# Cell_Connections.net
KiCad netlist of a schematic drawn in Altium Designer
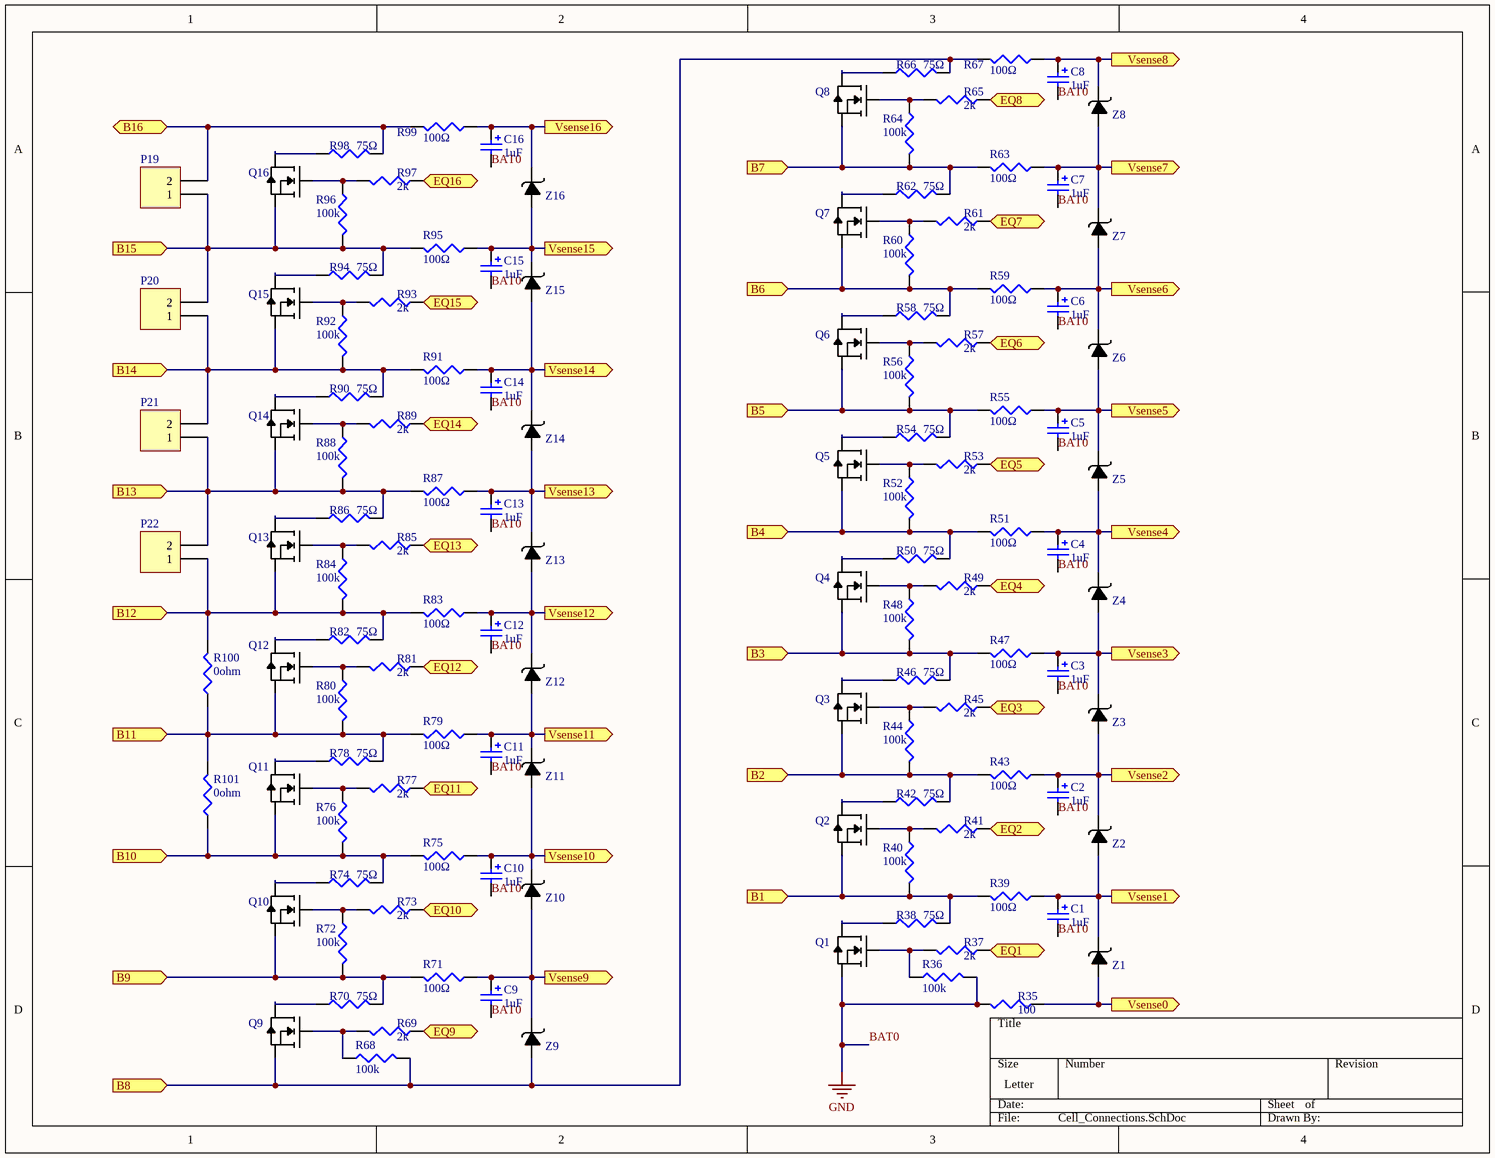
[diagram p0: Cell_Connections.SchDoc]

(export (version "E")
  (design (tool "Eeschema 10.0.6"))
  (components
    (comp (ref "C1")
      (value "1uF")
      (footprint "SMD1206 Polarized")
      (description "Polarized Capacitor (Surface Mount)")
      (fields (field (name "Comment") "Cap"))
      (libsource (lib "Components") (part "Capacitor Polarized"))
    )
    (comp (ref "C2")
      (value "1uF")
      (footprint "SMD1206 Polarized")
      (description "Polarized Capacitor (Surface Mount)")
      (fields (field (name "Comment") "Cap"))
      (libsource (lib "Components") (part "Capacitor Polarized"))
    )
    (comp (ref "C3")
      (value "1uF")
      (footprint "SMD1206 Polarized")
      (description "Polarized Capacitor (Surface Mount)")
      (fields (field (name "Comment") "Cap"))
      (libsource (lib "Components") (part "Capacitor Polarized"))
    )
    (comp (ref "C4")
      (value "1uF")
      (footprint "SMD1206 Polarized")
      (description "Polarized Capacitor (Surface Mount)")
      (fields (field (name "Comment") "Cap"))
      (libsource (lib "Components") (part "Capacitor Polarized"))
    )
    (comp (ref "C5")
      (value "1uF")
      (footprint "SMD1206 Polarized")
      (description "Polarized Capacitor (Surface Mount)")
      (fields (field (name "Comment") "Cap"))
      (libsource (lib "Components") (part "Capacitor Polarized"))
    )
    (comp (ref "C6")
      (value "1uF")
      (footprint "SMD1206 Polarized")
      (description "Polarized Capacitor (Surface Mount)")
      (fields (field (name "Comment") "Cap"))
      (libsource (lib "Components") (part "Capacitor Polarized"))
    )
    (comp (ref "C7")
      (value "1uF")
      (footprint "SMD1206 Polarized")
      (description "Polarized Capacitor (Surface Mount)")
      (fields (field (name "Comment") "Cap"))
      (libsource (lib "Components") (part "Capacitor Polarized"))
    )
    (comp (ref "C8")
      (value "1uF")
      (footprint "SMD1206 Polarized")
      (description "Polarized Capacitor (Surface Mount)")
      (fields (field (name "Comment") "Cap"))
      (libsource (lib "Components") (part "Capacitor Polarized"))
    )
    (comp (ref "C9")
      (value "1uF")
      (footprint "SMD1206 Polarized")
      (description "Polarized Capacitor (Surface Mount)")
      (fields (field (name "Comment") "Cap"))
      (libsource (lib "Components") (part "Capacitor Polarized"))
    )
    (comp (ref "C10")
      (value "1uF")
      (footprint "SMD1206 Polarized")
      (description "Polarized Capacitor (Surface Mount)")
      (fields (field (name "Comment") "Cap"))
      (libsource (lib "Components") (part "Capacitor Polarized"))
    )
    (comp (ref "C11")
      (value "1uF")
      (footprint "SMD1206 Polarized")
      (description "Polarized Capacitor (Surface Mount)")
      (fields (field (name "Comment") "Cap"))
      (libsource (lib "Components") (part "Capacitor Polarized"))
    )
    (comp (ref "C12")
      (value "1uF")
      (footprint "SMD1206 Polarized")
      (description "Polarized Capacitor (Surface Mount)")
      (fields (field (name "Comment") "Cap"))
      (libsource (lib "Components") (part "Capacitor Polarized"))
    )
    (comp (ref "C13")
      (value "1uF")
      (footprint "SMD1206 Polarized")
      (description "Polarized Capacitor (Surface Mount)")
      (fields (field (name "Comment") "Cap"))
      (libsource (lib "Components") (part "Capacitor Polarized"))
    )
    (comp (ref "C14")
      (value "1uF")
      (footprint "SMD1206 Polarized")
      (description "Polarized Capacitor (Surface Mount)")
      (fields (field (name "Comment") "Cap"))
      (libsource (lib "Components") (part "Capacitor Polarized"))
    )
    (comp (ref "C15")
      (value "1uF")
      (footprint "SMD1206 Polarized")
      (description "Polarized Capacitor (Surface Mount)")
      (fields (field (name "Comment") "Cap"))
      (libsource (lib "Components") (part "Capacitor Polarized"))
    )
    (comp (ref "C16")
      (value "1uF")
      (footprint "SMD1206 Polarized")
      (description "Polarized Capacitor (Surface Mount)")
      (fields (field (name "Comment") "Cap"))
      (libsource (lib "Components") (part "Capacitor Polarized"))
    )
    (comp (ref "P19")
      (value "Header")
      (footprint "Header 2x1")
      (description "Header, 2-Pin")
      (libsource (lib "Components") (part "Header 2x1"))
    )
    (comp (ref "P20")
      (value "Header")
      (footprint "Header 2x1")
      (description "Header, 2-Pin")
      (libsource (lib "Components") (part "Header 2x1"))
    )
    (comp (ref "P21")
      (value "Header")
      (footprint "Header 2x1")
      (description "Header, 2-Pin")
      (libsource (lib "Components") (part "Header 2x1"))
    )
    (comp (ref "P22")
      (value "Header")
      (footprint "Header 2x1")
      (description "Header, 2-Pin")
      (libsource (lib "Components") (part "Header 2x1"))
    )
    (comp (ref "Q1")
      (value "Transistor")
      (footprint "DPAK M:Transistor 3-Lead")
      (libsource (lib "Components") (part "Transistor"))
    )
    (comp (ref "Q2")
      (value "Transistor")
      (footprint "DPAK M:Transistor 3-Lead")
      (libsource (lib "Components") (part "Transistor"))
    )
    (comp (ref "Q3")
      (value "Transistor")
      (footprint "DPAK M:Transistor 3-Lead")
      (libsource (lib "Components") (part "Transistor"))
    )
    (comp (ref "Q4")
      (value "Transistor")
      (footprint "DPAK M:Transistor 3-Lead")
      (libsource (lib "Components") (part "Transistor"))
    )
    (comp (ref "Q5")
      (value "Transistor")
      (footprint "DPAK M:Transistor 3-Lead")
      (libsource (lib "Components") (part "Transistor"))
    )
    (comp (ref "Q6")
      (value "Transistor")
      (footprint "DPAK M:Transistor 3-Lead")
      (libsource (lib "Components") (part "Transistor"))
    )
    (comp (ref "Q7")
      (value "Transistor")
      (footprint "DPAK M:Transistor 3-Lead")
      (libsource (lib "Components") (part "Transistor"))
    )
    (comp (ref "Q8")
      (value "Transistor")
      (footprint "DPAK M:Transistor 3-Lead")
      (libsource (lib "Components") (part "Transistor"))
    )
    (comp (ref "Q9")
      (value "Transistor")
      (footprint "DPAK M:Transistor 3-Lead")
      (libsource (lib "Components") (part "Transistor"))
    )
    (comp (ref "Q10")
      (value "Transistor")
      (footprint "DPAK M:Transistor 3-Lead")
      (libsource (lib "Components") (part "Transistor"))
    )
    (comp (ref "Q11")
      (value "Transistor")
      (footprint "DPAK M:Transistor 3-Lead")
      (libsource (lib "Components") (part "Transistor"))
    )
    (comp (ref "Q12")
      (value "Transistor")
      (footprint "DPAK M:Transistor 3-Lead")
      (libsource (lib "Components") (part "Transistor"))
    )
    (comp (ref "Q13")
      (value "Transistor")
      (footprint "DPAK M:Transistor 3-Lead")
      (libsource (lib "Components") (part "Transistor"))
    )
    (comp (ref "Q14")
      (value "Transistor")
      (footprint "DPAK M:Transistor 3-Lead")
      (libsource (lib "Components") (part "Transistor"))
    )
    (comp (ref "Q15")
      (value "Transistor")
      (footprint "DPAK M:Transistor 3-Lead")
      (libsource (lib "Components") (part "Transistor"))
    )
    (comp (ref "Q16")
      (value "Transistor")
      (footprint "DPAK M:Transistor 3-Lead")
      (libsource (lib "Components") (part "Transistor"))
    )
    (comp (ref "R35")
      (value "100")
      (footprint "SMD0603")
      (description "Resistor")
      (fields (field (name "Comment") "Res"))
      (libsource (lib "Components") (part "Resistor"))
    )
    (comp (ref "R36")
      (value "100k")
      (footprint "SMD0603")
      (description "Resistor")
      (fields (field (name "Comment") "Res"))
      (libsource (lib "Components") (part "Resistor"))
    )
    (comp (ref "R37")
      (value "2k")
      (footprint "SMD0603")
      (description "Resistor")
      (fields (field (name "Comment") "Res"))
      (libsource (lib "Components") (part "Resistor"))
    )
    (comp (ref "R38")
      (value "75Ω")
      (footprint "SMD0603")
      (description "Resistor")
      (fields (field (name "Comment") "Res"))
      (libsource (lib "Components") (part "Resistor"))
    )
    (comp (ref "R39")
      (value "100Ω")
      (footprint "SMD0603")
      (description "Resistor")
      (fields (field (name "Comment") "Res"))
      (libsource (lib "Components") (part "Resistor"))
    )
    (comp (ref "R40")
      (value "100k")
      (footprint "SMD0603")
      (description "Resistor")
      (fields (field (name "Comment") "Res"))
      (libsource (lib "Components") (part "Resistor"))
    )
    (comp (ref "R41")
      (value "2k")
      (footprint "SMD0603")
      (description "Resistor")
      (fields (field (name "Comment") "Res"))
      (libsource (lib "Components") (part "Resistor"))
    )
    (comp (ref "R42")
      (value "75Ω")
      (footprint "SMD0603")
      (description "Resistor")
      (fields (field (name "Comment") "Res"))
      (libsource (lib "Components") (part "Resistor"))
    )
    (comp (ref "R43")
      (value "100Ω")
      (footprint "SMD0603")
      (description "Resistor")
      (fields (field (name "Comment") "Res"))
      (libsource (lib "Components") (part "Resistor"))
    )
    (comp (ref "R44")
      (value "100k")
      (footprint "SMD0603")
      (description "Resistor")
      (fields (field (name "Comment") "Res"))
      (libsource (lib "Components") (part "Resistor"))
    )
    (comp (ref "R45")
      (value "2k")
      (footprint "SMD0603")
      (description "Resistor")
      (fields (field (name "Comment") "Res"))
      (libsource (lib "Components") (part "Resistor"))
    )
    (comp (ref "R46")
      (value "75Ω")
      (footprint "SMD0603")
      (description "Resistor")
      (fields (field (name "Comment") "Res"))
      (libsource (lib "Components") (part "Resistor"))
    )
    (comp (ref "R47")
      (value "100Ω")
      (footprint "SMD0603")
      (description "Resistor")
      (fields (field (name "Comment") "Res"))
      (libsource (lib "Components") (part "Resistor"))
    )
    (comp (ref "R48")
      (value "100k")
      (footprint "SMD0603")
      (description "Resistor")
      (fields (field (name "Comment") "Res"))
      (libsource (lib "Components") (part "Resistor"))
    )
    (comp (ref "R49")
      (value "2k")
      (footprint "SMD0603")
      (description "Resistor")
      (fields (field (name "Comment") "Res"))
      (libsource (lib "Components") (part "Resistor"))
    )
    (comp (ref "R50")
      (value "75Ω")
      (footprint "SMD0603")
      (description "Resistor")
      (fields (field (name "Comment") "Res"))
      (libsource (lib "Components") (part "Resistor"))
    )
    (comp (ref "R51")
      (value "100Ω")
      (footprint "SMD0603")
      (description "Resistor")
      (fields (field (name "Comment") "Res"))
      (libsource (lib "Components") (part "Resistor"))
    )
    (comp (ref "R52")
      (value "100k")
      (footprint "SMD0603")
      (description "Resistor")
      (fields (field (name "Comment") "Res"))
      (libsource (lib "Components") (part "Resistor"))
    )
    (comp (ref "R53")
      (value "2k")
      (footprint "SMD0603")
      (description "Resistor")
      (fields (field (name "Comment") "Res"))
      (libsource (lib "Components") (part "Resistor"))
    )
    (comp (ref "R54")
      (value "75Ω")
      (footprint "SMD0603")
      (description "Resistor")
      (fields (field (name "Comment") "Res"))
      (libsource (lib "Components") (part "Resistor"))
    )
    (comp (ref "R55")
      (value "100Ω")
      (footprint "SMD0603")
      (description "Resistor")
      (fields (field (name "Comment") "Res"))
      (libsource (lib "Components") (part "Resistor"))
    )
    (comp (ref "R56")
      (value "100k")
      (footprint "SMD0603")
      (description "Resistor")
      (fields (field (name "Comment") "Res"))
      (libsource (lib "Components") (part "Resistor"))
    )
    (comp (ref "R57")
      (value "2k")
      (footprint "SMD0603")
      (description "Resistor")
      (fields (field (name "Comment") "Res"))
      (libsource (lib "Components") (part "Resistor"))
    )
    (comp (ref "R58")
      (value "75Ω")
      (footprint "SMD0603")
      (description "Resistor")
      (fields (field (name "Comment") "Res"))
      (libsource (lib "Components") (part "Resistor"))
    )
    (comp (ref "R59")
      (value "100Ω")
      (footprint "SMD0603")
      (description "Resistor")
      (fields (field (name "Comment") "Res"))
      (libsource (lib "Components") (part "Resistor"))
    )
    (comp (ref "R60")
      (value "100k")
      (footprint "SMD0603")
      (description "Resistor")
      (fields (field (name "Comment") "Res"))
      (libsource (lib "Components") (part "Resistor"))
    )
    (comp (ref "R61")
      (value "2k")
      (footprint "SMD0603")
      (description "Resistor")
      (fields (field (name "Comment") "Res"))
      (libsource (lib "Components") (part "Resistor"))
    )
    (comp (ref "R62")
      (value "75Ω")
      (footprint "SMD0603")
      (description "Resistor")
      (fields (field (name "Comment") "Res"))
      (libsource (lib "Components") (part "Resistor"))
    )
    (comp (ref "R63")
      (value "100Ω")
      (footprint "SMD0603")
      (description "Resistor")
      (fields (field (name "Comment") "Res"))
      (libsource (lib "Components") (part "Resistor"))
    )
    (comp (ref "R64")
      (value "100k")
      (footprint "SMD0603")
      (description "Resistor")
      (fields (field (name "Comment") "Res"))
      (libsource (lib "Components") (part "Resistor"))
    )
    (comp (ref "R65")
      (value "2k")
      (footprint "SMD0603")
      (description "Resistor")
      (fields (field (name "Comment") "Res"))
      (libsource (lib "Components") (part "Resistor"))
    )
    (comp (ref "R66")
      (value "75Ω")
      (footprint "SMD0603")
      (description "Resistor")
      (fields (field (name "Comment") "Res"))
      (libsource (lib "Components") (part "Resistor"))
    )
    (comp (ref "R67")
      (value "100Ω")
      (footprint "SMD0603")
      (description "Resistor")
      (fields (field (name "Comment") "Res"))
      (libsource (lib "Components") (part "Resistor"))
    )
    (comp (ref "R68")
      (value "100k")
      (footprint "SMD0603")
      (description "Resistor")
      (fields (field (name "Comment") "Res"))
      (libsource (lib "Components") (part "Resistor"))
    )
    (comp (ref "R69")
      (value "2k")
      (footprint "SMD0603")
      (description "Resistor")
      (fields (field (name "Comment") "Res"))
      (libsource (lib "Components") (part "Resistor"))
    )
    (comp (ref "R70")
      (value "75Ω")
      (footprint "SMD0603")
      (description "Resistor")
      (fields (field (name "Comment") "Res"))
      (libsource (lib "Components") (part "Resistor"))
    )
    (comp (ref "R71")
      (value "100Ω")
      (footprint "SMD0603")
      (description "Resistor")
      (fields (field (name "Comment") "Res"))
      (libsource (lib "Components") (part "Resistor"))
    )
    (comp (ref "R72")
      (value "100k")
      (footprint "SMD0603")
      (description "Resistor")
      (fields (field (name "Comment") "Res"))
      (libsource (lib "Components") (part "Resistor"))
    )
    (comp (ref "R73")
      (value "2k")
      (footprint "SMD0603")
      (description "Resistor")
      (fields (field (name "Comment") "Res"))
      (libsource (lib "Components") (part "Resistor"))
    )
    (comp (ref "R74")
      (value "75Ω")
      (footprint "SMD0603")
      (description "Resistor")
      (fields (field (name "Comment") "Res"))
      (libsource (lib "Components") (part "Resistor"))
    )
    (comp (ref "R75")
      (value "100Ω")
      (footprint "SMD0603")
      (description "Resistor")
      (fields (field (name "Comment") "Res"))
      (libsource (lib "Components") (part "Resistor"))
    )
    (comp (ref "R76")
      (value "100k")
      (footprint "SMD0603")
      (description "Resistor")
      (fields (field (name "Comment") "Res"))
      (libsource (lib "Components") (part "Resistor"))
    )
    (comp (ref "R77")
      (value "2k")
      (footprint "SMD0603")
      (description "Resistor")
      (fields (field (name "Comment") "Res"))
      (libsource (lib "Components") (part "Resistor"))
    )
    (comp (ref "R78")
      (value "75Ω")
      (footprint "SMD0603")
      (description "Resistor")
      (fields (field (name "Comment") "Res"))
      (libsource (lib "Components") (part "Resistor"))
    )
    (comp (ref "R79")
      (value "100Ω")
      (footprint "SMD0603")
      (description "Resistor")
      (fields (field (name "Comment") "Res"))
      (libsource (lib "Components") (part "Resistor"))
    )
    (comp (ref "R80")
      (value "100k")
      (footprint "SMD0603")
      (description "Resistor")
      (fields (field (name "Comment") "Res"))
      (libsource (lib "Components") (part "Resistor"))
    )
    (comp (ref "R81")
      (value "2k")
      (footprint "SMD0603")
      (description "Resistor")
      (fields (field (name "Comment") "Res"))
      (libsource (lib "Components") (part "Resistor"))
    )
    (comp (ref "R82")
      (value "75Ω")
      (footprint "SMD0603")
      (description "Resistor")
      (fields (field (name "Comment") "Res"))
      (libsource (lib "Components") (part "Resistor"))
    )
    (comp (ref "R83")
      (value "100Ω")
      (footprint "SMD0603")
      (description "Resistor")
      (fields (field (name "Comment") "Res"))
      (libsource (lib "Components") (part "Resistor"))
    )
    (comp (ref "R84")
      (value "100k")
      (footprint "SMD0603")
      (description "Resistor")
      (fields (field (name "Comment") "Res"))
      (libsource (lib "Components") (part "Resistor"))
    )
    (comp (ref "R85")
      (value "2k")
      (footprint "SMD0603")
      (description "Resistor")
      (fields (field (name "Comment") "Res"))
      (libsource (lib "Components") (part "Resistor"))
    )
    (comp (ref "R86")
      (value "75Ω")
      (footprint "SMD0603")
      (description "Resistor")
      (fields (field (name "Comment") "Res"))
      (libsource (lib "Components") (part "Resistor"))
    )
    (comp (ref "R87")
      (value "100Ω")
      (footprint "SMD0603")
      (description "Resistor")
      (fields (field (name "Comment") "Res"))
      (libsource (lib "Components") (part "Resistor"))
    )
    (comp (ref "R88")
      (value "100k")
      (footprint "SMD0603")
      (description "Resistor")
      (fields (field (name "Comment") "Res"))
      (libsource (lib "Components") (part "Resistor"))
    )
    (comp (ref "R89")
      (value "2k")
      (footprint "SMD0603")
      (description "Resistor")
      (fields (field (name "Comment") "Res"))
      (libsource (lib "Components") (part "Resistor"))
    )
    (comp (ref "R90")
      (value "75Ω")
      (footprint "SMD0603")
      (description "Resistor")
      (fields (field (name "Comment") "Res"))
      (libsource (lib "Components") (part "Resistor"))
    )
    (comp (ref "R91")
      (value "100Ω")
      (footprint "SMD0603")
      (description "Resistor")
      (fields (field (name "Comment") "Res"))
      (libsource (lib "Components") (part "Resistor"))
    )
    (comp (ref "R92")
      (value "100k")
      (footprint "SMD0603")
      (description "Resistor")
      (fields (field (name "Comment") "Res"))
      (libsource (lib "Components") (part "Resistor"))
    )
    (comp (ref "R93")
      (value "2k")
      (footprint "SMD0603")
      (description "Resistor")
      (fields (field (name "Comment") "Res"))
      (libsource (lib "Components") (part "Resistor"))
    )
    (comp (ref "R94")
      (value "75Ω")
      (footprint "SMD0603")
      (description "Resistor")
      (fields (field (name "Comment") "Res"))
      (libsource (lib "Components") (part "Resistor"))
    )
    (comp (ref "R95")
      (value "100Ω")
      (footprint "SMD0603")
      (description "Resistor")
      (fields (field (name "Comment") "Res"))
      (libsource (lib "Components") (part "Resistor"))
    )
    (comp (ref "R96")
      (value "100k")
      (footprint "SMD0603")
      (description "Resistor")
      (fields (field (name "Comment") "Res"))
      (libsource (lib "Components") (part "Resistor"))
    )
    (comp (ref "R97")
      (value "2k")
      (footprint "SMD0603")
      (description "Resistor")
      (fields (field (name "Comment") "Res"))
      (libsource (lib "Components") (part "Resistor"))
    )
    (comp (ref "R98")
      (value "75Ω")
      (footprint "SMD0603")
      (description "Resistor")
      (fields (field (name "Comment") "Res"))
      (libsource (lib "Components") (part "Resistor"))
    )
    (comp (ref "R99")
      (value "100Ω")
      (footprint "SMD0603")
      (description "Resistor")
      (fields (field (name "Comment") "Res"))
      (libsource (lib "Components") (part "Resistor"))
    )
    (comp (ref "R100")
      (value "0ohm")
      (footprint "SMD0603")
      (description "Resistor")
      (fields (field (name "Comment") "Res"))
      (libsource (lib "Components") (part "Resistor"))
    )
    (comp (ref "R101")
      (value "0ohm")
      (footprint "SMD0603")
      (description "Resistor")
      (fields (field (name "Comment") "Res"))
      (libsource (lib "Components") (part "Resistor"))
    )
    (comp (ref "Z1")
      (value "Zener Diode")
      (footprint "DPAK M:ZenerCell")
      (libsource (lib "Components") (part "Zener Diode"))
    )
    (comp (ref "Z2")
      (value "Zener Diode")
      (footprint "DPAK M:ZenerCell")
      (libsource (lib "Components") (part "Zener Diode"))
    )
    (comp (ref "Z3")
      (value "Zener Diode")
      (footprint "DPAK M:ZenerCell")
      (libsource (lib "Components") (part "Zener Diode"))
    )
    (comp (ref "Z4")
      (value "Zener Diode")
      (footprint "DPAK M:ZenerCell")
      (libsource (lib "Components") (part "Zener Diode"))
    )
    (comp (ref "Z5")
      (value "Zener Diode")
      (footprint "DPAK M:ZenerCell")
      (libsource (lib "Components") (part "Zener Diode"))
    )
    (comp (ref "Z6")
      (value "Zener Diode")
      (footprint "DPAK M:ZenerCell")
      (libsource (lib "Components") (part "Zener Diode"))
    )
    (comp (ref "Z7")
      (value "Zener Diode")
      (footprint "DPAK M:ZenerCell")
      (libsource (lib "Components") (part "Zener Diode"))
    )
    (comp (ref "Z8")
      (value "Zener Diode")
      (footprint "DPAK M:ZenerCell")
      (libsource (lib "Components") (part "Zener Diode"))
    )
    (comp (ref "Z9")
      (value "Zener Diode")
      (footprint "DPAK M:ZenerCell")
      (libsource (lib "Components") (part "Zener Diode"))
    )
    (comp (ref "Z10")
      (value "Zener Diode")
      (footprint "DPAK M:ZenerCell")
      (libsource (lib "Components") (part "Zener Diode"))
    )
    (comp (ref "Z11")
      (value "Zener Diode")
      (footprint "DPAK M:ZenerCell")
      (libsource (lib "Components") (part "Zener Diode"))
    )
    (comp (ref "Z12")
      (value "Zener Diode")
      (footprint "DPAK M:ZenerCell")
      (libsource (lib "Components") (part "Zener Diode"))
    )
    (comp (ref "Z13")
      (value "Zener Diode")
      (footprint "DPAK M:ZenerCell")
      (libsource (lib "Components") (part "Zener Diode"))
    )
    (comp (ref "Z14")
      (value "Zener Diode")
      (footprint "DPAK M:ZenerCell")
      (libsource (lib "Components") (part "Zener Diode"))
    )
    (comp (ref "Z15")
      (value "Zener Diode")
      (footprint "DPAK M:ZenerCell")
      (libsource (lib "Components") (part "Zener Diode"))
    )
    (comp (ref "Z16")
      (value "Zener Diode")
      (footprint "DPAK M:ZenerCell")
      (libsource (lib "Components") (part "Zener Diode"))
    )
  )
  (nets
    (net (code "1") (name "/B1") (class "Default")
      (node (ref "Q2") (pin "3") (pinfunction "S_3") (pintype "passive"))
      (node (ref "R38") (pin "2") (pinfunction "2_2") (pintype "passive"))
      (node (ref "R39") (pin "2") (pinfunction "2_2") (pintype "passive"))
      (node (ref "R40") (pin "2") (pinfunction "2_2") (pintype "passive"))
    )
    (net (code "2") (name "/B2") (class "Default")
      (node (ref "Q3") (pin "3") (pinfunction "S_3") (pintype "passive"))
      (node (ref "R42") (pin "2") (pinfunction "2_2") (pintype "passive"))
      (node (ref "R43") (pin "2") (pinfunction "2_2") (pintype "passive"))
      (node (ref "R44") (pin "2") (pinfunction "2_2") (pintype "passive"))
    )
    (net (code "3") (name "/B3") (class "Default")
      (node (ref "Q4") (pin "3") (pinfunction "S_3") (pintype "passive"))
      (node (ref "R46") (pin "2") (pinfunction "2_2") (pintype "passive"))
      (node (ref "R47") (pin "2") (pinfunction "2_2") (pintype "passive"))
      (node (ref "R48") (pin "2") (pinfunction "2_2") (pintype "passive"))
    )
    (net (code "4") (name "/B4") (class "Default")
      (node (ref "Q5") (pin "3") (pinfunction "S_3") (pintype "passive"))
      (node (ref "R50") (pin "2") (pinfunction "2_2") (pintype "passive"))
      (node (ref "R51") (pin "2") (pinfunction "2_2") (pintype "passive"))
      (node (ref "R52") (pin "2") (pinfunction "2_2") (pintype "passive"))
    )
    (net (code "5") (name "/B5") (class "Default")
      (node (ref "Q6") (pin "3") (pinfunction "S_3") (pintype "passive"))
      (node (ref "R54") (pin "2") (pinfunction "2_2") (pintype "passive"))
      (node (ref "R55") (pin "2") (pinfunction "2_2") (pintype "passive"))
      (node (ref "R56") (pin "2") (pinfunction "2_2") (pintype "passive"))
    )
    (net (code "6") (name "/B6") (class "Default")
      (node (ref "Q7") (pin "3") (pinfunction "S_3") (pintype "passive"))
      (node (ref "R58") (pin "2") (pinfunction "2_2") (pintype "passive"))
      (node (ref "R59") (pin "2") (pinfunction "2_2") (pintype "passive"))
      (node (ref "R60") (pin "2") (pinfunction "2_2") (pintype "passive"))
    )
    (net (code "7") (name "/B7") (class "Default")
      (node (ref "Q8") (pin "3") (pinfunction "S_3") (pintype "passive"))
      (node (ref "R62") (pin "2") (pinfunction "2_2") (pintype "passive"))
      (node (ref "R63") (pin "2") (pinfunction "2_2") (pintype "passive"))
      (node (ref "R64") (pin "2") (pinfunction "2_2") (pintype "passive"))
    )
    (net (code "8") (name "/B8") (class "Default")
      (node (ref "Q9") (pin "3") (pinfunction "S_3") (pintype "passive"))
      (node (ref "R66") (pin "2") (pinfunction "2_2") (pintype "passive"))
      (node (ref "R67") (pin "2") (pinfunction "2_2") (pintype "passive"))
      (node (ref "R68") (pin "2") (pinfunction "2_2") (pintype "passive"))
      (node (ref "Z9") (pin "1") (pintype "passive"))
    )
    (net (code "9") (name "/B9") (class "Default")
      (node (ref "Q10") (pin "3") (pinfunction "S_3") (pintype "passive"))
      (node (ref "R70") (pin "2") (pinfunction "2_2") (pintype "passive"))
      (node (ref "R71") (pin "2") (pinfunction "2_2") (pintype "passive"))
      (node (ref "R72") (pin "2") (pinfunction "2_2") (pintype "passive"))
    )
    (net (code "10") (name "/B10") (class "Default")
      (node (ref "Q11") (pin "3") (pinfunction "S_3") (pintype "passive"))
      (node (ref "R101") (pin "1") (pinfunction "1_1") (pintype "passive"))
      (node (ref "R74") (pin "2") (pinfunction "2_2") (pintype "passive"))
      (node (ref "R75") (pin "2") (pinfunction "2_2") (pintype "passive"))
      (node (ref "R76") (pin "2") (pinfunction "2_2") (pintype "passive"))
    )
    (net (code "11") (name "/B11") (class "Default")
      (node (ref "Q12") (pin "3") (pinfunction "S_3") (pintype "passive"))
      (node (ref "R100") (pin "1") (pinfunction "1_1") (pintype "passive"))
      (node (ref "R101") (pin "2") (pinfunction "2_2") (pintype "passive"))
      (node (ref "R78") (pin "2") (pinfunction "2_2") (pintype "passive"))
      (node (ref "R79") (pin "2") (pinfunction "2_2") (pintype "passive"))
      (node (ref "R80") (pin "2") (pinfunction "2_2") (pintype "passive"))
    )
    (net (code "12") (name "/B12") (class "Default")
      (node (ref "P22") (pin "1") (pinfunction "1_1") (pintype "passive"))
      (node (ref "Q13") (pin "3") (pinfunction "S_3") (pintype "passive"))
      (node (ref "R100") (pin "2") (pinfunction "2_2") (pintype "passive"))
      (node (ref "R82") (pin "2") (pinfunction "2_2") (pintype "passive"))
      (node (ref "R83") (pin "2") (pinfunction "2_2") (pintype "passive"))
      (node (ref "R84") (pin "2") (pinfunction "2_2") (pintype "passive"))
    )
    (net (code "13") (name "/B13") (class "Default")
      (node (ref "P21") (pin "1") (pinfunction "1_1") (pintype "passive"))
      (node (ref "P22") (pin "2") (pinfunction "2_2") (pintype "passive"))
      (node (ref "Q14") (pin "3") (pinfunction "S_3") (pintype "passive"))
      (node (ref "R86") (pin "2") (pinfunction "2_2") (pintype "passive"))
      (node (ref "R87") (pin "2") (pinfunction "2_2") (pintype "passive"))
      (node (ref "R88") (pin "2") (pinfunction "2_2") (pintype "passive"))
    )
    (net (code "14") (name "/B14") (class "Default")
      (node (ref "P20") (pin "1") (pinfunction "1_1") (pintype "passive"))
      (node (ref "P21") (pin "2") (pinfunction "2_2") (pintype "passive"))
      (node (ref "Q15") (pin "3") (pinfunction "S_3") (pintype "passive"))
      (node (ref "R90") (pin "2") (pinfunction "2_2") (pintype "passive"))
      (node (ref "R91") (pin "2") (pinfunction "2_2") (pintype "passive"))
      (node (ref "R92") (pin "2") (pinfunction "2_2") (pintype "passive"))
    )
    (net (code "15") (name "/B15") (class "Default")
      (node (ref "P19") (pin "1") (pinfunction "1_1") (pintype "passive"))
      (node (ref "P20") (pin "2") (pinfunction "2_2") (pintype "passive"))
      (node (ref "Q16") (pin "3") (pinfunction "S_3") (pintype "passive"))
      (node (ref "R94") (pin "2") (pinfunction "2_2") (pintype "passive"))
      (node (ref "R95") (pin "2") (pinfunction "2_2") (pintype "passive"))
      (node (ref "R96") (pin "2") (pinfunction "2_2") (pintype "passive"))
    )
    (net (code "16") (name "/B16") (class "Default")
      (node (ref "P19") (pin "2") (pinfunction "2_2") (pintype "passive"))
      (node (ref "R98") (pin "2") (pinfunction "2_2") (pintype "passive"))
      (node (ref "R99") (pin "2") (pinfunction "2_2") (pintype "passive"))
    )
    (net (code "17") (name "/EQ1") (class "Default")
      (node (ref "R37") (pin "1") (pinfunction "1_1") (pintype "passive"))
    )
    (net (code "18") (name "/EQ2") (class "Default")
      (node (ref "R41") (pin "1") (pinfunction "1_1") (pintype "passive"))
    )
    (net (code "19") (name "/EQ3") (class "Default")
      (node (ref "R45") (pin "1") (pinfunction "1_1") (pintype "passive"))
    )
    (net (code "20") (name "/EQ4") (class "Default")
      (node (ref "R49") (pin "1") (pinfunction "1_1") (pintype "passive"))
    )
    (net (code "21") (name "/EQ5") (class "Default")
      (node (ref "R53") (pin "1") (pinfunction "1_1") (pintype "passive"))
    )
    (net (code "22") (name "/EQ6") (class "Default")
      (node (ref "R57") (pin "1") (pinfunction "1_1") (pintype "passive"))
    )
    (net (code "23") (name "/EQ7") (class "Default")
      (node (ref "R61") (pin "1") (pinfunction "1_1") (pintype "passive"))
    )
    (net (code "24") (name "/EQ8") (class "Default")
      (node (ref "R65") (pin "1") (pinfunction "1_1") (pintype "passive"))
    )
    (net (code "25") (name "/EQ9") (class "Default")
      (node (ref "R69") (pin "1") (pinfunction "1_1") (pintype "passive"))
    )
    (net (code "26") (name "/EQ10") (class "Default")
      (node (ref "R73") (pin "1") (pinfunction "1_1") (pintype "passive"))
    )
    (net (code "27") (name "/EQ11") (class "Default")
      (node (ref "R77") (pin "1") (pinfunction "1_1") (pintype "passive"))
    )
    (net (code "28") (name "/EQ12") (class "Default")
      (node (ref "R81") (pin "1") (pinfunction "1_1") (pintype "passive"))
    )
    (net (code "29") (name "/EQ13") (class "Default")
      (node (ref "R85") (pin "1") (pinfunction "1_1") (pintype "passive"))
    )
    (net (code "30") (name "/EQ14") (class "Default")
      (node (ref "R89") (pin "1") (pinfunction "1_1") (pintype "passive"))
    )
    (net (code "31") (name "/EQ15") (class "Default")
      (node (ref "R93") (pin "1") (pinfunction "1_1") (pintype "passive"))
    )
    (net (code "32") (name "/EQ16") (class "Default")
      (node (ref "R97") (pin "1") (pinfunction "1_1") (pintype "passive"))
    )
    (net (code "33") (name "/Vsense0") (class "Default")
      (node (ref "R35") (pin "1") (pinfunction "1_1") (pintype "passive"))
      (node (ref "Z1") (pin "1") (pintype "passive"))
    )
    (net (code "34") (name "/Vsense1") (class "Default")
      (node (ref "C1") (pin "1") (pinfunction "1_1") (pintype "passive"))
      (node (ref "R39") (pin "1") (pinfunction "1_1") (pintype "passive"))
      (node (ref "Z1") (pin "2") (pinfunction "2_2") (pintype "passive"))
      (node (ref "Z2") (pin "1") (pintype "passive"))
    )
    (net (code "35") (name "/Vsense2") (class "Default")
      (node (ref "C2") (pin "1") (pinfunction "1_1") (pintype "passive"))
      (node (ref "R43") (pin "1") (pinfunction "1_1") (pintype "passive"))
      (node (ref "Z2") (pin "2") (pinfunction "2_2") (pintype "passive"))
      (node (ref "Z3") (pin "1") (pintype "passive"))
    )
    (net (code "36") (name "/Vsense3") (class "Default")
      (node (ref "C3") (pin "1") (pinfunction "1_1") (pintype "passive"))
      (node (ref "R47") (pin "1") (pinfunction "1_1") (pintype "passive"))
      (node (ref "Z3") (pin "2") (pinfunction "2_2") (pintype "passive"))
      (node (ref "Z4") (pin "1") (pintype "passive"))
    )
    (net (code "37") (name "/Vsense4") (class "Default")
      (node (ref "C4") (pin "1") (pinfunction "1_1") (pintype "passive"))
      (node (ref "R51") (pin "1") (pinfunction "1_1") (pintype "passive"))
      (node (ref "Z4") (pin "2") (pinfunction "2_2") (pintype "passive"))
      (node (ref "Z5") (pin "1") (pintype "passive"))
    )
    (net (code "38") (name "/Vsense5") (class "Default")
      (node (ref "C5") (pin "1") (pinfunction "1_1") (pintype "passive"))
      (node (ref "R55") (pin "1") (pinfunction "1_1") (pintype "passive"))
      (node (ref "Z5") (pin "2") (pinfunction "2_2") (pintype "passive"))
      (node (ref "Z6") (pin "1") (pintype "passive"))
    )
    (net (code "39") (name "/Vsense6") (class "Default")
      (node (ref "C6") (pin "1") (pinfunction "1_1") (pintype "passive"))
      (node (ref "R59") (pin "1") (pinfunction "1_1") (pintype "passive"))
      (node (ref "Z6") (pin "2") (pinfunction "2_2") (pintype "passive"))
      (node (ref "Z7") (pin "1") (pintype "passive"))
    )
    (net (code "40") (name "/Vsense7") (class "Default")
      (node (ref "C7") (pin "1") (pinfunction "1_1") (pintype "passive"))
      (node (ref "R63") (pin "1") (pinfunction "1_1") (pintype "passive"))
      (node (ref "Z7") (pin "2") (pinfunction "2_2") (pintype "passive"))
      (node (ref "Z8") (pin "1") (pintype "passive"))
    )
    (net (code "41") (name "/Vsense8") (class "Default")
      (node (ref "C8") (pin "1") (pinfunction "1_1") (pintype "passive"))
      (node (ref "R67") (pin "1") (pinfunction "1_1") (pintype "passive"))
      (node (ref "Z8") (pin "2") (pinfunction "2_2") (pintype "passive"))
    )
    (net (code "42") (name "/Vsense9") (class "Default")
      (node (ref "C9") (pin "1") (pinfunction "1_1") (pintype "passive"))
      (node (ref "R71") (pin "1") (pinfunction "1_1") (pintype "passive"))
      (node (ref "Z10") (pin "1") (pintype "passive"))
      (node (ref "Z9") (pin "2") (pinfunction "2_2") (pintype "passive"))
    )
    (net (code "43") (name "/Vsense10") (class "Default")
      (node (ref "C10") (pin "1") (pinfunction "1_1") (pintype "passive"))
      (node (ref "R75") (pin "1") (pinfunction "1_1") (pintype "passive"))
      (node (ref "Z10") (pin "2") (pinfunction "2_2") (pintype "passive"))
      (node (ref "Z11") (pin "1") (pintype "passive"))
    )
    (net (code "44") (name "/Vsense11") (class "Default")
      (node (ref "C11") (pin "1") (pinfunction "1_1") (pintype "passive"))
      (node (ref "R79") (pin "1") (pinfunction "1_1") (pintype "passive"))
      (node (ref "Z11") (pin "2") (pinfunction "2_2") (pintype "passive"))
      (node (ref "Z12") (pin "1") (pintype "passive"))
    )
    (net (code "45") (name "/Vsense12") (class "Default")
      (node (ref "C12") (pin "1") (pinfunction "1_1") (pintype "passive"))
      (node (ref "R83") (pin "1") (pinfunction "1_1") (pintype "passive"))
      (node (ref "Z12") (pin "2") (pinfunction "2_2") (pintype "passive"))
      (node (ref "Z13") (pin "1") (pintype "passive"))
    )
    (net (code "46") (name "/Vsense13") (class "Default")
      (node (ref "C13") (pin "1") (pinfunction "1_1") (pintype "passive"))
      (node (ref "R87") (pin "1") (pinfunction "1_1") (pintype "passive"))
      (node (ref "Z13") (pin "2") (pinfunction "2_2") (pintype "passive"))
      (node (ref "Z14") (pin "1") (pintype "passive"))
    )
    (net (code "47") (name "/Vsense14") (class "Default")
      (node (ref "C14") (pin "1") (pinfunction "1_1") (pintype "passive"))
      (node (ref "R91") (pin "1") (pinfunction "1_1") (pintype "passive"))
      (node (ref "Z14") (pin "2") (pinfunction "2_2") (pintype "passive"))
      (node (ref "Z15") (pin "1") (pintype "passive"))
    )
    (net (code "48") (name "/Vsense15") (class "Default")
      (node (ref "C15") (pin "1") (pinfunction "1_1") (pintype "passive"))
      (node (ref "R95") (pin "1") (pinfunction "1_1") (pintype "passive"))
      (node (ref "Z15") (pin "2") (pinfunction "2_2") (pintype "passive"))
      (node (ref "Z16") (pin "1") (pintype "passive"))
    )
    (net (code "49") (name "/Vsense16") (class "Default")
      (node (ref "C16") (pin "1") (pinfunction "1_1") (pintype "passive"))
      (node (ref "R99") (pin "1") (pinfunction "1_1") (pintype "passive"))
      (node (ref "Z16") (pin "2") (pinfunction "2_2") (pintype "passive"))
    )
    (net (code "50") (name "GND") (class "Default")
      (node (ref "C1") (pin "2") (pinfunction "2_2") (pintype "passive"))
      (node (ref "C10") (pin "2") (pinfunction "2_2") (pintype "passive"))
      (node (ref "C11") (pin "2") (pinfunction "2_2") (pintype "passive"))
      (node (ref "C12") (pin "2") (pinfunction "2_2") (pintype "passive"))
      (node (ref "C13") (pin "2") (pinfunction "2_2") (pintype "passive"))
      (node (ref "C14") (pin "2") (pinfunction "2_2") (pintype "passive"))
      (node (ref "C15") (pin "2") (pinfunction "2_2") (pintype "passive"))
      (node (ref "C16") (pin "2") (pinfunction "2_2") (pintype "passive"))
      (node (ref "C2") (pin "2") (pinfunction "2_2") (pintype "passive"))
      (node (ref "C3") (pin "2") (pinfunction "2_2") (pintype "passive"))
      (node (ref "C4") (pin "2") (pinfunction "2_2") (pintype "passive"))
      (node (ref "C5") (pin "2") (pinfunction "2_2") (pintype "passive"))
      (node (ref "C6") (pin "2") (pinfunction "2_2") (pintype "passive"))
      (node (ref "C7") (pin "2") (pinfunction "2_2") (pintype "passive"))
      (node (ref "C8") (pin "2") (pinfunction "2_2") (pintype "passive"))
      (node (ref "C9") (pin "2") (pinfunction "2_2") (pintype "passive"))
      (node (ref "Q1") (pin "3") (pinfunction "S_3") (pintype "passive"))
      (node (ref "R35") (pin "2") (pinfunction "2_2") (pintype "passive"))
      (node (ref "R36") (pin "2") (pinfunction "2_2") (pintype "passive"))
    )
    (net (code "51") (name "Net-(Q1-D)") (class "Default")
      (node (ref "Q1") (pin "1") (pinfunction "D_1") (pintype "passive"))
      (node (ref "R38") (pin "1") (pinfunction "1_1") (pintype "passive"))
    )
    (net (code "52") (name "Net-(Q1-G)") (class "Default")
      (node (ref "Q1") (pin "2") (pinfunction "G_2") (pintype "passive"))
      (node (ref "R36") (pin "1") (pinfunction "1_1") (pintype "passive"))
      (node (ref "R37") (pin "2") (pinfunction "2_2") (pintype "passive"))
    )
    (net (code "53") (name "Net-(Q2-D)") (class "Default")
      (node (ref "Q2") (pin "1") (pinfunction "D_1") (pintype "passive"))
      (node (ref "R42") (pin "1") (pinfunction "1_1") (pintype "passive"))
    )
    (net (code "54") (name "Net-(Q2-G)") (class "Default")
      (node (ref "Q2") (pin "2") (pinfunction "G_2") (pintype "passive"))
      (node (ref "R40") (pin "1") (pinfunction "1_1") (pintype "passive"))
      (node (ref "R41") (pin "2") (pinfunction "2_2") (pintype "passive"))
    )
    (net (code "55") (name "Net-(Q3-D)") (class "Default")
      (node (ref "Q3") (pin "1") (pinfunction "D_1") (pintype "passive"))
      (node (ref "R46") (pin "1") (pinfunction "1_1") (pintype "passive"))
    )
    (net (code "56") (name "Net-(Q3-G)") (class "Default")
      (node (ref "Q3") (pin "2") (pinfunction "G_2") (pintype "passive"))
      (node (ref "R44") (pin "1") (pinfunction "1_1") (pintype "passive"))
      (node (ref "R45") (pin "2") (pinfunction "2_2") (pintype "passive"))
    )
    (net (code "57") (name "Net-(Q4-D)") (class "Default")
      (node (ref "Q4") (pin "1") (pinfunction "D_1") (pintype "passive"))
      (node (ref "R50") (pin "1") (pinfunction "1_1") (pintype "passive"))
    )
    (net (code "58") (name "Net-(Q4-G)") (class "Default")
      (node (ref "Q4") (pin "2") (pinfunction "G_2") (pintype "passive"))
      (node (ref "R48") (pin "1") (pinfunction "1_1") (pintype "passive"))
      (node (ref "R49") (pin "2") (pinfunction "2_2") (pintype "passive"))
    )
    (net (code "59") (name "Net-(Q5-D)") (class "Default")
      (node (ref "Q5") (pin "1") (pinfunction "D_1") (pintype "passive"))
      (node (ref "R54") (pin "1") (pinfunction "1_1") (pintype "passive"))
    )
    (net (code "60") (name "Net-(Q5-G)") (class "Default")
      (node (ref "Q5") (pin "2") (pinfunction "G_2") (pintype "passive"))
      (node (ref "R52") (pin "1") (pinfunction "1_1") (pintype "passive"))
      (node (ref "R53") (pin "2") (pinfunction "2_2") (pintype "passive"))
    )
    (net (code "61") (name "Net-(Q6-D)") (class "Default")
      (node (ref "Q6") (pin "1") (pinfunction "D_1") (pintype "passive"))
      (node (ref "R58") (pin "1") (pinfunction "1_1") (pintype "passive"))
    )
    (net (code "62") (name "Net-(Q6-G)") (class "Default")
      (node (ref "Q6") (pin "2") (pinfunction "G_2") (pintype "passive"))
      (node (ref "R56") (pin "1") (pinfunction "1_1") (pintype "passive"))
      (node (ref "R57") (pin "2") (pinfunction "2_2") (pintype "passive"))
    )
    (net (code "63") (name "Net-(Q7-D)") (class "Default")
      (node (ref "Q7") (pin "1") (pinfunction "D_1") (pintype "passive"))
      (node (ref "R62") (pin "1") (pinfunction "1_1") (pintype "passive"))
    )
    (net (code "64") (name "Net-(Q7-G)") (class "Default")
      (node (ref "Q7") (pin "2") (pinfunction "G_2") (pintype "passive"))
      (node (ref "R60") (pin "1") (pinfunction "1_1") (pintype "passive"))
      (node (ref "R61") (pin "2") (pinfunction "2_2") (pintype "passive"))
    )
    (net (code "65") (name "Net-(Q8-D)") (class "Default")
      (node (ref "Q8") (pin "1") (pinfunction "D_1") (pintype "passive"))
      (node (ref "R66") (pin "1") (pinfunction "1_1") (pintype "passive"))
    )
    (net (code "66") (name "Net-(Q8-G)") (class "Default")
      (node (ref "Q8") (pin "2") (pinfunction "G_2") (pintype "passive"))
      (node (ref "R64") (pin "1") (pinfunction "1_1") (pintype "passive"))
      (node (ref "R65") (pin "2") (pinfunction "2_2") (pintype "passive"))
    )
    (net (code "67") (name "Net-(Q9-D)") (class "Default")
      (node (ref "Q9") (pin "1") (pinfunction "D_1") (pintype "passive"))
      (node (ref "R70") (pin "1") (pinfunction "1_1") (pintype "passive"))
    )
    (net (code "68") (name "Net-(Q9-G)") (class "Default")
      (node (ref "Q9") (pin "2") (pinfunction "G_2") (pintype "passive"))
      (node (ref "R68") (pin "1") (pinfunction "1_1") (pintype "passive"))
      (node (ref "R69") (pin "2") (pinfunction "2_2") (pintype "passive"))
    )
    (net (code "69") (name "Net-(Q10-D)") (class "Default")
      (node (ref "Q10") (pin "1") (pinfunction "D_1") (pintype "passive"))
      (node (ref "R74") (pin "1") (pinfunction "1_1") (pintype "passive"))
    )
    (net (code "70") (name "Net-(Q10-G)") (class "Default")
      (node (ref "Q10") (pin "2") (pinfunction "G_2") (pintype "passive"))
      (node (ref "R72") (pin "1") (pinfunction "1_1") (pintype "passive"))
      (node (ref "R73") (pin "2") (pinfunction "2_2") (pintype "passive"))
    )
    (net (code "71") (name "Net-(Q11-D)") (class "Default")
      (node (ref "Q11") (pin "1") (pinfunction "D_1") (pintype "passive"))
      (node (ref "R78") (pin "1") (pinfunction "1_1") (pintype "passive"))
    )
    (net (code "72") (name "Net-(Q11-G)") (class "Default")
      (node (ref "Q11") (pin "2") (pinfunction "G_2") (pintype "passive"))
      (node (ref "R76") (pin "1") (pinfunction "1_1") (pintype "passive"))
      (node (ref "R77") (pin "2") (pinfunction "2_2") (pintype "passive"))
    )
    (net (code "73") (name "Net-(Q12-D)") (class "Default")
      (node (ref "Q12") (pin "1") (pinfunction "D_1") (pintype "passive"))
      (node (ref "R82") (pin "1") (pinfunction "1_1") (pintype "passive"))
    )
    (net (code "74") (name "Net-(Q12-G)") (class "Default")
      (node (ref "Q12") (pin "2") (pinfunction "G_2") (pintype "passive"))
      (node (ref "R80") (pin "1") (pinfunction "1_1") (pintype "passive"))
      (node (ref "R81") (pin "2") (pinfunction "2_2") (pintype "passive"))
    )
    (net (code "75") (name "Net-(Q13-D)") (class "Default")
      (node (ref "Q13") (pin "1") (pinfunction "D_1") (pintype "passive"))
      (node (ref "R86") (pin "1") (pinfunction "1_1") (pintype "passive"))
    )
    (net (code "76") (name "Net-(Q13-G)") (class "Default")
      (node (ref "Q13") (pin "2") (pinfunction "G_2") (pintype "passive"))
      (node (ref "R84") (pin "1") (pinfunction "1_1") (pintype "passive"))
      (node (ref "R85") (pin "2") (pinfunction "2_2") (pintype "passive"))
    )
    (net (code "77") (name "Net-(Q14-D)") (class "Default")
      (node (ref "Q14") (pin "1") (pinfunction "D_1") (pintype "passive"))
      (node (ref "R90") (pin "1") (pinfunction "1_1") (pintype "passive"))
    )
    (net (code "78") (name "Net-(Q14-G)") (class "Default")
      (node (ref "Q14") (pin "2") (pinfunction "G_2") (pintype "passive"))
      (node (ref "R88") (pin "1") (pinfunction "1_1") (pintype "passive"))
      (node (ref "R89") (pin "2") (pinfunction "2_2") (pintype "passive"))
    )
    (net (code "79") (name "Net-(Q15-D)") (class "Default")
      (node (ref "Q15") (pin "1") (pinfunction "D_1") (pintype "passive"))
      (node (ref "R94") (pin "1") (pinfunction "1_1") (pintype "passive"))
    )
    (net (code "80") (name "Net-(Q15-G)") (class "Default")
      (node (ref "Q15") (pin "2") (pinfunction "G_2") (pintype "passive"))
      (node (ref "R92") (pin "1") (pinfunction "1_1") (pintype "passive"))
      (node (ref "R93") (pin "2") (pinfunction "2_2") (pintype "passive"))
    )
    (net (code "81") (name "Net-(Q16-D)") (class "Default")
      (node (ref "Q16") (pin "1") (pinfunction "D_1") (pintype "passive"))
      (node (ref "R98") (pin "1") (pinfunction "1_1") (pintype "passive"))
    )
    (net (code "82") (name "Net-(Q16-G)") (class "Default")
      (node (ref "Q16") (pin "2") (pinfunction "G_2") (pintype "passive"))
      (node (ref "R96") (pin "1") (pinfunction "1_1") (pintype "passive"))
      (node (ref "R97") (pin "2") (pinfunction "2_2") (pintype "passive"))
    )
  )
)
